# BLE113_module.net
KiCad netlist of a schematic drawn in Altium Designer
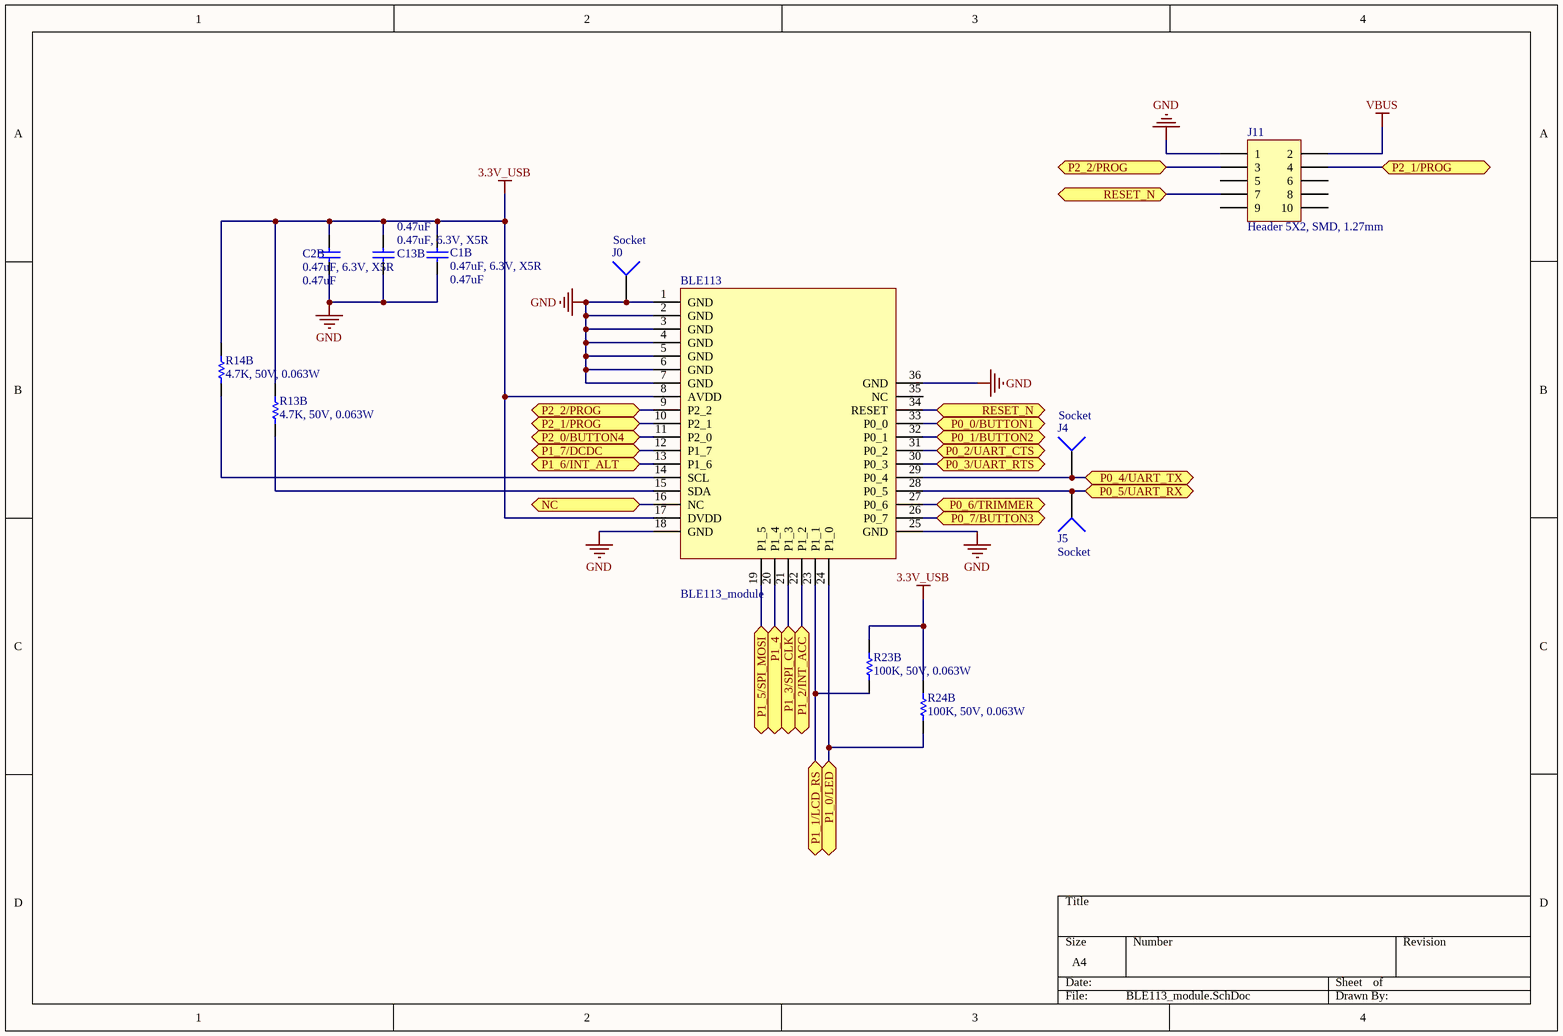
[diagram p0: BLE113_module.SchDoc]

(export (version "E")
  (design (tool "Eeschema 10.0.6"))
  (components
    (comp (ref "BLE113")
      (value "BLE113_module")
      (footprint "DKB113:BLE113 module")
      (libsource (lib "DKB113") (part "BLE113_module"))
    )
    (comp (ref "C1B")
      (value "0.47uF, 6.3V, X5R")
      (footprint "C0805")
      (description "Capacitor (Semiconductor SIM Model)")
      (fields (field (name "ALTIUM_VALUE") "0.47uF") (field (name "PUBLISHER") "Altium Limited"))
      (libsource (lib "Miscellaneous Devices") (part "Cap Semi"))
    )
    (comp (ref "C2B")
      (value "0.47uF, 6.3V, X5R")
      (footprint "C0805")
      (description "Capacitor (Semiconductor SIM Model)")
      (fields (field (name "ALTIUM_VALUE") "0.47uF") (field (name "PUBLISHER") "Altium Limited"))
      (libsource (lib "Miscellaneous Devices") (part "Cap Semi"))
    )
    (comp (ref "C13B")
      (value "0.47uF, 6.3V, X5R")
      (footprint "C0805")
      (description "Capacitor (Semiconductor SIM Model)")
      (fields (field (name "ALTIUM_VALUE") "0.47uF") (field (name "PUBLISHER") "Altium Limited"))
      (libsource (lib "Miscellaneous Devices") (part "Cap Semi"))
    )
    (comp (ref "J0")
      (value "Socket")
      (footprint "PIN1")
      (fields (field (name "PUBLISHER") "Altium Limited"))
      (libsource (lib "Miscellaneous Connectors") (part "Socket"))
    )
    (comp (ref "J4")
      (value "Socket")
      (footprint "PIN1")
      (fields (field (name "PUBLISHER") "Altium Limited"))
      (libsource (lib "Miscellaneous Connectors") (part "Socket"))
    )
    (comp (ref "J5")
      (value "Socket")
      (footprint "PIN1")
      (fields (field (name "PUBLISHER") "Altium Limited"))
      (libsource (lib "Miscellaneous Connectors") (part "Socket"))
    )
    (comp (ref "J11")
      (value "Header 5X2, SMD, 1.27mm")
      (footprint "MHDR2X5")
      (description "Header, 5-Pin, Dual row")
      (fields (field (name "PUBLISHER") "Altium Limited"))
      (libsource (lib "Miscellaneous Connectors") (part "MHDR2X5"))
    )
    (comp (ref "R13B")
      (value "4.7K, 50V, 0.063W")
      (footprint "ERA-0805")
      (fields (field (name "PUBLISHER") "Altium Limited"))
      (libsource (lib "Panasonic Resistor") (part "ERAS"))
    )
    (comp (ref "R14B")
      (value "4.7K, 50V, 0.063W")
      (footprint "ERA-0805")
      (fields (field (name "PUBLISHER") "Altium Limited"))
      (libsource (lib "Panasonic Resistor") (part "ERAS"))
    )
    (comp (ref "R23B")
      (value "100K, 50V, 0.063W")
      (footprint "ERA-0805")
      (fields (field (name "PUBLISHER") "Altium Limited"))
      (libsource (lib "Panasonic Resistor") (part "ERAS"))
    )
    (comp (ref "R24B")
      (value "100K, 50V, 0.063W")
      (footprint "ERA-0805")
      (fields (field (name "PUBLISHER") "Altium Limited"))
      (libsource (lib "Panasonic Resistor") (part "ERAS"))
    )
  )
  (nets
    (net (code "1") (name "/NC") (class "Default")
      (node (ref "BLE113") (pin "16") (pinfunction "NC_16") (pintype "passive"))
    )
    (net (code "2") (name "/P0_0{slash}BUTTON1") (class "Default")
      (node (ref "BLE113") (pin "33") (pinfunction "P0_0_33") (pintype "passive"))
    )
    (net (code "3") (name "/P0_1{slash}BUTTON2") (class "Default")
      (node (ref "BLE113") (pin "32") (pinfunction "P0_1_32") (pintype "passive"))
    )
    (net (code "4") (name "/P0_2{slash}UART_CTS") (class "Default")
      (node (ref "BLE113") (pin "31") (pinfunction "P0_2_31") (pintype "passive"))
    )
    (net (code "5") (name "/P0_3{slash}UART_RTS") (class "Default")
      (node (ref "BLE113") (pin "30") (pinfunction "P0_3_30") (pintype "passive"))
    )
    (net (code "6") (name "/P0_4{slash}UART_TX") (class "Default")
      (node (ref "BLE113") (pin "29") (pinfunction "P0_4_29") (pintype "passive"))
      (node (ref "J4") (pin "1") (pinfunction "1_1") (pintype "passive"))
    )
    (net (code "7") (name "/P0_5{slash}UART_RX") (class "Default")
      (node (ref "BLE113") (pin "28") (pinfunction "P0_5_28") (pintype "passive"))
      (node (ref "J5") (pin "1") (pinfunction "1_1") (pintype "passive"))
    )
    (net (code "8") (name "/P0_6{slash}TRIMMER") (class "Default")
      (node (ref "BLE113") (pin "27") (pinfunction "P0_6_27") (pintype "passive"))
    )
    (net (code "9") (name "/P0_7{slash}BUTTON3") (class "Default")
      (node (ref "BLE113") (pin "26") (pinfunction "P0_7_26") (pintype "passive"))
    )
    (net (code "10") (name "/P1_0{slash}LED") (class "Default")
      (node (ref "BLE113") (pin "24") (pinfunction "P1_0_24") (pintype "passive"))
      (node (ref "R24B") (pin "1") (pinfunction "1_1") (pintype "passive"))
    )
    (net (code "11") (name "/P1_1{slash}LCD_RS") (class "Default")
      (node (ref "BLE113") (pin "23") (pinfunction "P1_1_23") (pintype "passive"))
      (node (ref "R23B") (pin "1") (pinfunction "1_1") (pintype "passive"))
    )
    (net (code "12") (name "/P1_2{slash}INT_ACC") (class "Default")
      (node (ref "BLE113") (pin "22") (pinfunction "P1_2_22") (pintype "passive"))
    )
    (net (code "13") (name "/P1_3{slash}SPI_CLK") (class "Default")
      (node (ref "BLE113") (pin "21") (pinfunction "P1_3_21") (pintype "passive"))
    )
    (net (code "14") (name "/P1_4") (class "Default")
      (node (ref "BLE113") (pin "20") (pinfunction "P1_4_20") (pintype "passive"))
    )
    (net (code "15") (name "/P1_5{slash}SPI_MOSI") (class "Default")
      (node (ref "BLE113") (pin "19") (pinfunction "P1_5_19") (pintype "passive"))
    )
    (net (code "16") (name "/P1_6{slash}INT_ALT") (class "Default")
      (node (ref "BLE113") (pin "13") (pinfunction "P1_6_13") (pintype "passive"))
    )
    (net (code "17") (name "/P1_7{slash}DCDC") (class "Default")
      (node (ref "BLE113") (pin "12") (pinfunction "P1_7_12") (pintype "passive"))
    )
    (net (code "18") (name "/P2_0{slash}BUTTON4") (class "Default")
      (node (ref "BLE113") (pin "11") (pinfunction "P2_0_11") (pintype "passive"))
    )
    (net (code "19") (name "/P2_1{slash}PROG") (class "Default")
      (node (ref "BLE113") (pin "10") (pinfunction "P2_1_10") (pintype "passive"))
      (node (ref "J11") (pin "4") (pinfunction "4_4") (pintype "passive"))
    )
    (net (code "20") (name "/P2_2{slash}PROG") (class "Default")
      (node (ref "BLE113") (pin "9") (pinfunction "P2_2_9") (pintype "passive"))
      (node (ref "J11") (pin "3") (pinfunction "3_3") (pintype "passive"))
    )
    (net (code "21") (name "/RESET_N") (class "Default")
      (node (ref "BLE113") (pin "34") (pinfunction "RESET_34") (pintype "passive"))
      (node (ref "J11") (pin "7") (pinfunction "7_7") (pintype "passive"))
    )
    (net (code "22") (name "3.3V_USB") (class "Default")
      (node (ref "BLE113") (pin "17") (pinfunction "DVDD_17") (pintype "passive"))
      (node (ref "BLE113") (pin "8") (pinfunction "AVDD_8") (pintype "passive"))
      (node (ref "C13B") (pin "2") (pinfunction "2_2") (pintype "passive"))
      (node (ref "C1B") (pin "2") (pinfunction "2_2") (pintype "passive"))
      (node (ref "C2B") (pin "2") (pinfunction "2_2") (pintype "passive"))
      (node (ref "R13B") (pin "2") (pinfunction "2_2") (pintype "passive"))
      (node (ref "R14B") (pin "2") (pinfunction "2_2") (pintype "passive"))
      (node (ref "R23B") (pin "2") (pinfunction "2_2") (pintype "passive"))
      (node (ref "R24B") (pin "2") (pinfunction "2_2") (pintype "passive"))
    )
    (net (code "23") (name "GND") (class "Default")
      (node (ref "BLE113") (pin "1") (pinfunction "GND_1") (pintype "passive"))
      (node (ref "BLE113") (pin "18") (pinfunction "GND_18") (pintype "passive"))
      (node (ref "BLE113") (pin "2") (pinfunction "GND_2") (pintype "passive"))
      (node (ref "BLE113") (pin "25") (pinfunction "GND_25") (pintype "passive"))
      (node (ref "BLE113") (pin "3") (pinfunction "GND_3") (pintype "passive"))
      (node (ref "BLE113") (pin "36") (pinfunction "GND_36") (pintype "passive"))
      (node (ref "BLE113") (pin "4") (pinfunction "GND_4") (pintype "passive"))
      (node (ref "BLE113") (pin "5") (pinfunction "GND_5") (pintype "passive"))
      (node (ref "BLE113") (pin "6") (pinfunction "GND_6") (pintype "passive"))
      (node (ref "BLE113") (pin "7") (pinfunction "GND_7") (pintype "passive"))
      (node (ref "C13B") (pin "1") (pinfunction "1_1") (pintype "passive"))
      (node (ref "C1B") (pin "1") (pinfunction "1_1") (pintype "passive"))
      (node (ref "C2B") (pin "1") (pinfunction "1_1") (pintype "passive"))
      (node (ref "J0") (pin "1") (pinfunction "1_1") (pintype "passive"))
      (node (ref "J11") (pin "1") (pinfunction "1_1") (pintype "passive"))
    )
    (net (code "24") (name "Net-(BLE113-SCL)") (class "Default")
      (node (ref "BLE113") (pin "14") (pinfunction "SCL_14") (pintype "passive"))
      (node (ref "R14B") (pin "1") (pinfunction "1_1") (pintype "passive"))
    )
    (net (code "25") (name "Net-(BLE113-SDA)") (class "Default")
      (node (ref "BLE113") (pin "15") (pinfunction "SDA_15") (pintype "passive"))
      (node (ref "R13B") (pin "1") (pinfunction "1_1") (pintype "passive"))
    )
    (net (code "26") (name "VBUS") (class "Default")
      (node (ref "J11") (pin "2") (pinfunction "2_2") (pintype "passive"))
    )
    (net (code "27") (name "unconnected-(BLE113-NC-Pad35)") (class "Default")
      (node (ref "BLE113") (pin "35") (pinfunction "NC_35") (pintype "passive"))
    )
    (net (code "28") (name "unconnected-(J11-Pad5)") (class "Default")
      (node (ref "J11") (pin "5") (pinfunction "5_5") (pintype "passive"))
    )
    (net (code "29") (name "unconnected-(J11-Pad6)") (class "Default")
      (node (ref "J11") (pin "6") (pinfunction "6_6") (pintype "passive"))
    )
    (net (code "30") (name "unconnected-(J11-Pad8)") (class "Default")
      (node (ref "J11") (pin "8") (pinfunction "8_8") (pintype "passive"))
    )
    (net (code "31") (name "unconnected-(J11-Pad9)") (class "Default")
      (node (ref "J11") (pin "9") (pinfunction "9_9") (pintype "passive"))
    )
    (net (code "32") (name "unconnected-(J11-Pad10)") (class "Default")
      (node (ref "J11") (pin "10") (pinfunction "10_10") (pintype "passive"))
    )
  )
)
